# ludi_cartridge_v1.net
KiCad netlist of a schematic drawn in Altium Designer
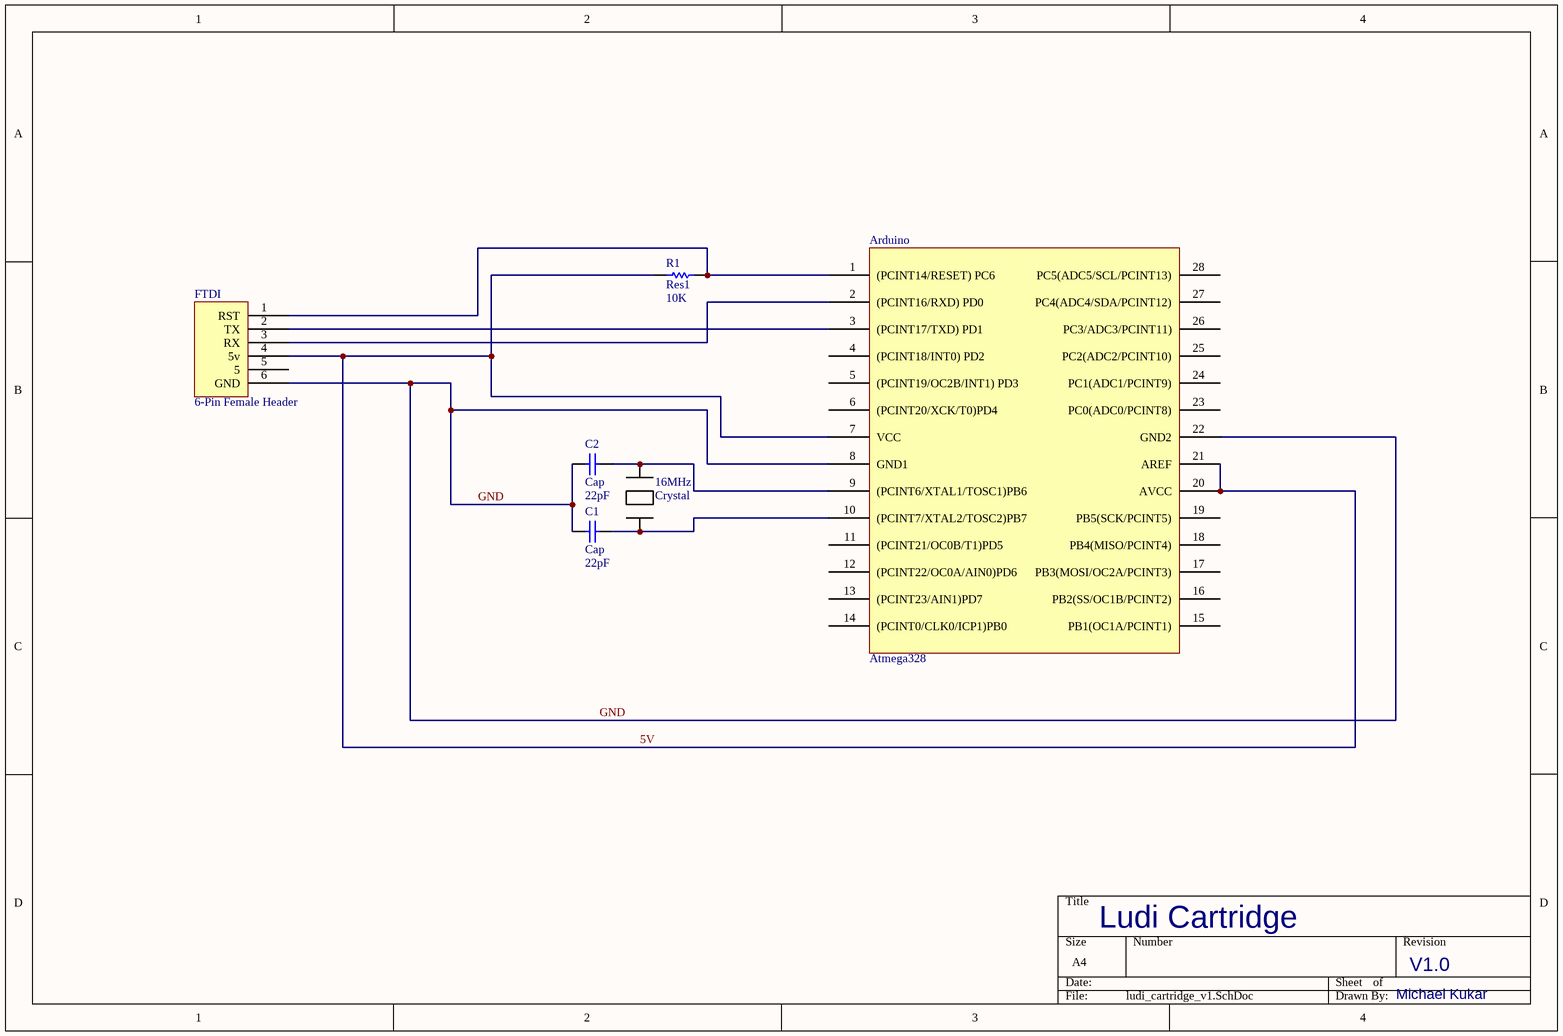
[diagram p0: ludi_cartridge_v1.SchDoc]

(export (version "E")
  (design (tool "Eeschema 10.0.6"))
  (components
    (comp (ref "16MHz")
      (value "Crystal")
      (footprint "Crystal - duplicate")
      (libsource (lib "ludi_cartridge_v1") (part "Crystal"))
    )
    (comp (ref "Arduino")
      (value "Atmega328")
      (footprint "AtmegaTQFP")
      (libsource (lib "ludi_cartridge_v1") (part "Atmega328"))
    )
    (comp (ref "C1")
      (value "Cap")
      (footprint ".1\" spacing")
      (description "Capacitor")
      (fields (field (name "ALTIUM_VALUE") "22pF") (field (name "PUBLISHER") "Altium Limited"))
      (libsource (lib "Miscellaneous Devices") (part "Cap"))
    )
    (comp (ref "C2")
      (value "Cap")
      (footprint ".1\" spacing")
      (description "Capacitor")
      (fields (field (name "ALTIUM_VALUE") "22pF") (field (name "PUBLISHER") "Altium Limited"))
      (libsource (lib "Miscellaneous Devices") (part "Cap"))
    )
    (comp (ref "FTDI")
      (value "6-Pin Female Header")
      (footprint "HDR1X6")
      (libsource (lib "ludi_cartridge_v1") (part "6-Pin Female Header"))
    )
    (comp (ref "R1")
      (value "Res1")
      (footprint "AXIAL-0.3")
      (description "Resistor")
      (fields (field (name "ALTIUM_VALUE") "10K") (field (name "PUBLISHER") "Altium Limited"))
      (libsource (lib "Miscellaneous Devices") (part "Res1"))
    )
  )
  (nets
    (net (code "1") (name "/5V") (class "Default")
      (node (ref "Arduino") (pin "20") (pinfunction "AVCC_20") (pintype "passive"))
      (node (ref "Arduino") (pin "21") (pinfunction "AREF_21") (pintype "passive"))
      (node (ref "Arduino") (pin "7") (pinfunction "VCC_7") (pintype "passive"))
      (node (ref "FTDI") (pin "4") (pinfunction "5v_4") (pintype "passive"))
      (node (ref "R1") (pin "1") (pinfunction "1_1") (pintype "passive"))
    )
    (net (code "2") (name "/GND") (class "Default")
      (node (ref "Arduino") (pin "22") (pinfunction "GND2_22") (pintype "passive"))
      (node (ref "Arduino") (pin "8") (pinfunction "GND1_8") (pintype "passive"))
      (node (ref "C1") (pin "1") (pinfunction "1_1") (pintype "passive"))
      (node (ref "C2") (pin "1") (pinfunction "1_1") (pintype "passive"))
      (node (ref "FTDI") (pin "6") (pinfunction "GND_6") (pintype "passive"))
    )
    (net (code "3") (name "Net-(16MHz-0)") (class "Default")
      (node (ref "16MHz") (pin "A") (pinfunction "0_A") (pintype "passive"))
      (node (ref "Arduino") (pin "9") (pinfunction "(PCINT6/XTAL1/TOSC1)PB6_9") (pintype "passive"))
      (node (ref "C2") (pin "2") (pinfunction "2_2") (pintype "passive"))
    )
    (net (code "4") (name "Net-(16MHz-1)") (class "Default")
      (node (ref "16MHz") (pin "K") (pinfunction "1_K") (pintype "passive"))
      (node (ref "Arduino") (pin "10") (pinfunction "(PCINT7/XTAL2/TOSC2)PB7_10") (pintype "passive"))
      (node (ref "C1") (pin "2") (pinfunction "2_2") (pintype "passive"))
    )
    (net (code "5") (name "Net-(Arduino-(PCINT14{slash}RESET)_PC6)") (class "Default")
      (node (ref "Arduino") (pin "1") (pinfunction "(PCINT14/RESET)_PC6_1") (pintype "passive"))
      (node (ref "FTDI") (pin "1") (pinfunction "RST_1") (pintype "passive"))
      (node (ref "R1") (pin "2") (pinfunction "2_2") (pintype "passive"))
    )
    (net (code "6") (name "Net-(Arduino-(PCINT16{slash}RXD)_PD0)") (class "Default")
      (node (ref "Arduino") (pin "2") (pinfunction "(PCINT16/RXD)_PD0_2") (pintype "passive"))
      (node (ref "FTDI") (pin "3") (pinfunction "RX_3") (pintype "passive"))
    )
    (net (code "7") (name "Net-(Arduino-(PCINT17{slash}TXD)_PD1)") (class "Default")
      (node (ref "Arduino") (pin "3") (pinfunction "(PCINT17/TXD)_PD1_3") (pintype "passive"))
      (node (ref "FTDI") (pin "2") (pinfunction "TX_2") (pintype "passive"))
    )
    (net (code "8") (name "unconnected-(Arduino-(PCINT0{slash}CLK0{slash}ICP1)PB0-Pad14)") (class "Default")
      (node (ref "Arduino") (pin "14") (pinfunction "(PCINT0/CLK0/ICP1)PB0_14") (pintype "passive"))
    )
    (net (code "9") (name "unconnected-(Arduino-(PCINT18{slash}INT0)_PD2-Pad4)") (class "Default")
      (node (ref "Arduino") (pin "4") (pinfunction "(PCINT18/INT0)_PD2_4") (pintype "passive"))
    )
    (net (code "10") (name "unconnected-(Arduino-(PCINT19{slash}OC2B{slash}INT1)_PD3-Pad5)") (class "Default")
      (node (ref "Arduino") (pin "5") (pinfunction "(PCINT19/OC2B/INT1)_PD3_5") (pintype "passive"))
    )
    (net (code "11") (name "unconnected-(Arduino-(PCINT20{slash}XCK{slash}T0)PD4-Pad6)") (class "Default")
      (node (ref "Arduino") (pin "6") (pinfunction "(PCINT20/XCK/T0)PD4_6") (pintype "passive"))
    )
    (net (code "12") (name "unconnected-(Arduino-(PCINT21{slash}OC0B{slash}T1)PD5-Pad11)") (class "Default")
      (node (ref "Arduino") (pin "11") (pinfunction "(PCINT21/OC0B/T1)PD5_11") (pintype "passive"))
    )
    (net (code "13") (name "unconnected-(Arduino-(PCINT22{slash}OC0A{slash}AIN0)PD6-Pad12)") (class "Default")
      (node (ref "Arduino") (pin "12") (pinfunction "(PCINT22/OC0A/AIN0)PD6_12") (pintype "passive"))
    )
    (net (code "14") (name "unconnected-(Arduino-(PCINT23{slash}AIN1)PD7-Pad13)") (class "Default")
      (node (ref "Arduino") (pin "13") (pinfunction "(PCINT23/AIN1)PD7_13") (pintype "passive"))
    )
    (net (code "15") (name "unconnected-(Arduino-PB1(OC1A{slash}PCINT1)-Pad15)") (class "Default")
      (node (ref "Arduino") (pin "15") (pinfunction "PB1(OC1A/PCINT1)_15") (pintype "passive"))
    )
    (net (code "16") (name "unconnected-(Arduino-PB2(SS{slash}OC1B{slash}PCINT2)-Pad16)") (class "Default")
      (node (ref "Arduino") (pin "16") (pinfunction "PB2(SS/OC1B/PCINT2)_16") (pintype "passive"))
    )
    (net (code "17") (name "unconnected-(Arduino-PB3(MOSI{slash}OC2A{slash}PCINT3)-Pad17)") (class "Default")
      (node (ref "Arduino") (pin "17") (pinfunction "PB3(MOSI/OC2A/PCINT3)_17") (pintype "passive"))
    )
    (net (code "18") (name "unconnected-(Arduino-PB4(MISO{slash}PCINT4)-Pad18)") (class "Default")
      (node (ref "Arduino") (pin "18") (pinfunction "PB4(MISO/PCINT4)_18") (pintype "passive"))
    )
    (net (code "19") (name "unconnected-(Arduino-PB5(SCK{slash}PCINT5)-Pad19)") (class "Default")
      (node (ref "Arduino") (pin "19") (pinfunction "PB5(SCK/PCINT5)_19") (pintype "passive"))
    )
    (net (code "20") (name "unconnected-(Arduino-PC0(ADC0{slash}PCINT8)-Pad23)") (class "Default")
      (node (ref "Arduino") (pin "23") (pinfunction "PC0(ADC0/PCINT8)_23") (pintype "passive"))
    )
    (net (code "21") (name "unconnected-(Arduino-PC1(ADC1{slash}PCINT9)-Pad24)") (class "Default")
      (node (ref "Arduino") (pin "24") (pinfunction "PC1(ADC1/PCINT9)_24") (pintype "passive"))
    )
    (net (code "22") (name "unconnected-(Arduino-PC2(ADC2{slash}PCINT10)-Pad25)") (class "Default")
      (node (ref "Arduino") (pin "25") (pinfunction "PC2(ADC2/PCINT10)_25") (pintype "passive"))
    )
    (net (code "23") (name "unconnected-(Arduino-PC3{slash}ADC3{slash}PCINT11)-Pad26)") (class "Default")
      (node (ref "Arduino") (pin "26") (pinfunction "PC3/ADC3/PCINT11)_26") (pintype "passive"))
    )
    (net (code "24") (name "unconnected-(Arduino-PC4(ADC4{slash}SDA{slash}PCINT12)-Pad27)") (class "Default")
      (node (ref "Arduino") (pin "27") (pinfunction "PC4(ADC4/SDA/PCINT12)_27") (pintype "passive"))
    )
    (net (code "25") (name "unconnected-(Arduino-PC5(ADC5{slash}SCL{slash}PCINT13)-Pad28)") (class "Default")
      (node (ref "Arduino") (pin "28") (pinfunction "PC5(ADC5/SCL/PCINT13)_28") (pintype "passive"))
    )
    (net (code "26") (name "unconnected-(FTDI-Pad5)") (class "Default")
      (node (ref "FTDI") (pin "5") (pinfunction "5_5") (pintype "passive"))
    )
  )
)
